# liuyang.net
KiCad netlist of a schematic drawn in Altium Designer
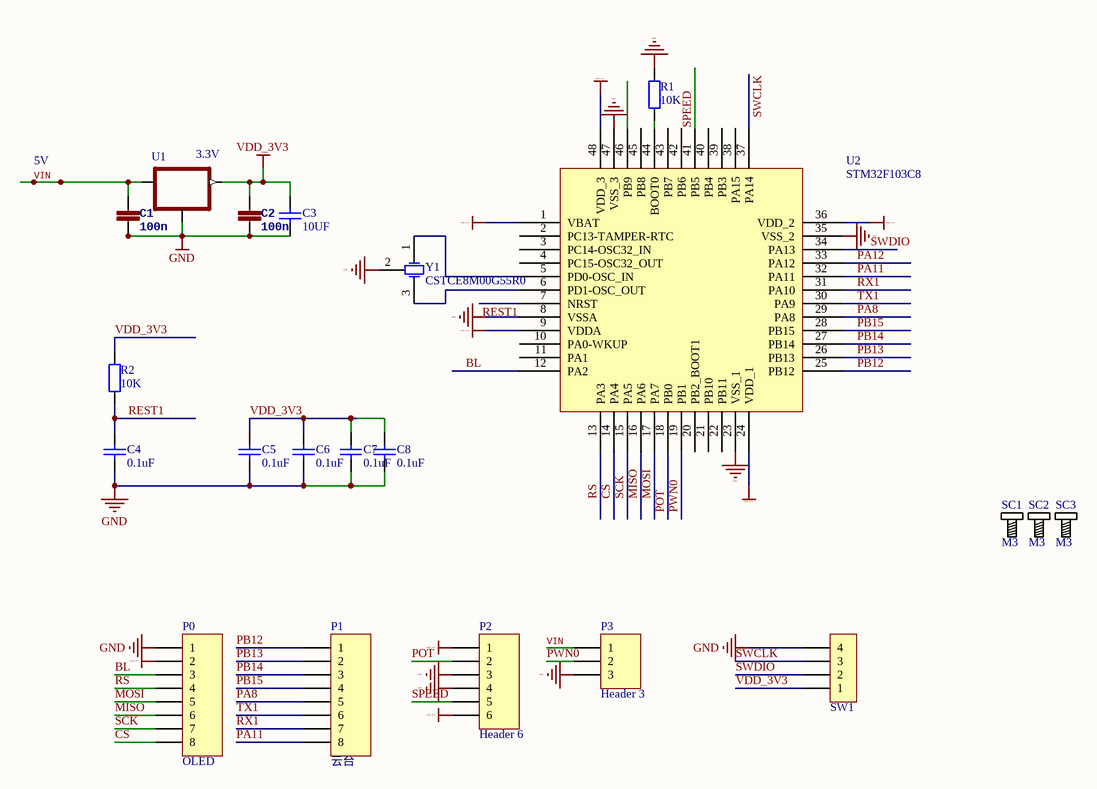
[diagram p0: liuyang.SchDoc]

(export (version "E")
  (design (tool "Eeschema 10.0.6"))
  (components
    (comp (ref "C1")
      (value "100n")
      (footprint "C0603")
      (description "CAPACITOR, European symbol")
      (libsource (lib "rcl") (part "C-EUC0603"))
    )
    (comp (ref "C2")
      (value "100n")
      (footprint "C0603")
      (description "CAPACITOR, European symbol")
      (libsource (lib "rcl") (part "C-EUC0603"))
    )
    (comp (ref "C3")
      (value "10UF")
      (footprint "C0603")
      (description "Capacitor")
      (fields (field (name "PUBLISHER") "Altium Limited"))
      (libsource (lib "Miscellaneous Devices") (part "Cap"))
    )
    (comp (ref "C4")
      (value "0.1uF")
      (footprint "C0603")
      (description "Capacitor")
      (fields (field (name "PUBLISHER") "Altium Limited"))
      (libsource (lib "Miscellaneous Devices") (part "Cap"))
    )
    (comp (ref "C5")
      (value "0.1uF")
      (footprint "C0603")
      (description "Capacitor")
      (fields (field (name "Comment") "10UF") (field (name "PUBLISHER") "Altium Limited"))
      (libsource (lib "Miscellaneous Devices") (part "Cap"))
    )
    (comp (ref "C6")
      (value "0.1uF")
      (footprint "C0603")
      (description "Capacitor")
      (fields (field (name "PUBLISHER") "Altium Limited"))
      (libsource (lib "Miscellaneous Devices") (part "Cap"))
    )
    (comp (ref "C7")
      (value "0.1uF")
      (footprint "C0603")
      (description "Capacitor")
      (fields (field (name "PUBLISHER") "Altium Limited"))
      (libsource (lib "Miscellaneous Devices") (part "Cap"))
    )
    (comp (ref "C8")
      (value "0.1uF")
      (footprint "C0603")
      (description "Capacitor")
      (fields (field (name "PUBLISHER") "Altium Limited"))
      (libsource (lib "Miscellaneous Devices") (part "Cap"))
    )
    (comp (ref "P0")
      (value "OLED")
      (footprint "DF13-1.25-8A")
      (description "Header, 8-Pin")
      (fields (field (name "PUBLISHER") "Altium Limited"))
      (libsource (lib "Miscellaneous Connectors") (part "Header 8"))
    )
    (comp (ref "P1")
      (value "云台")
      (footprint "DF13-1.25-8A")
      (description "Header, 8-Pin")
      (fields (field (name "PUBLISHER") "Altium Limited"))
      (libsource (lib "Miscellaneous Connectors") (part "Header 8"))
    )
    (comp (ref "P2")
      (value "Header 6")
      (footprint "DF13-1.25-6A")
      (description "Header, 6-Pin")
      (fields (field (name "PUBLISHER") "Altium Limited"))
      (libsource (lib "Miscellaneous Connectors") (part "Header 6"))
    )
    (comp (ref "P3")
      (value "Header 3")
      (footprint "DF13-1.25-3A")
      (description "Header, 3-Pin")
      (fields (field (name "PUBLISHER") "Altium Limited"))
      (libsource (lib "Miscellaneous Connectors") (part "Header 3"))
    )
    (comp (ref "R1")
      (value "10K")
      (footprint "R0603")
      (description "Resistor")
      (fields (field (name "PUBLISHER") "Altium Limited"))
      (libsource (lib "") (part "Res2_1"))
    )
    (comp (ref "R2")
      (value "10K")
      (footprint "R0603")
      (description "Resistor")
      (fields (field (name "PUBLISHER") "Altium Limited"))
      (libsource (lib "Miscellaneous Devices") (part "Res2"))
    )
    (comp (ref "SC1")
      (value "M3")
      (footprint "MYLIB:SCRREW_M3")
      (description "Screw")
      (libsource (lib "MY") (part "Screw_M3"))
    )
    (comp (ref "SC2")
      (value "M3")
      (footprint "SCRREW_M3")
      (description "Screw")
      (libsource (lib "MY") (part "Screw_M3"))
    )
    (comp (ref "SC3")
      (value "M3")
      (footprint "SCRREW_M3")
      (description "Screw")
      (libsource (lib "MY") (part "Screw_M3"))
    )
    (comp (ref "SW1") (value "CON4") (footprint "DF13-1.25-4A") (libsource (lib "原理图封装库") (part "CON4")))
    (comp (ref "U1") (value "3.3V") (footprint "SOT23") (libsource (lib "BGC1.0") (part "XC6206")))
    (comp (ref "U2")
      (value "STM32F103C8")
      (footprint "ST_LQFP48")
      (libsource (lib "airtops-L") (part "STM32F103C8"))
    )
    (comp (ref "Y1")
      (value "CSTCE8M00G55R0")
      (footprint "CRYSMD3.2X1.3")
      (libsource (lib "airtops-L") (part "XTAL-3"))
    )
  )
  (nets
    (net (code "1") (name "/BL") (class "Default")
      (node (ref "P0") (pin "3") (pinfunction "3_3") (pintype "passive"))
      (node (ref "U2") (pin "12") (pinfunction "PA2_12") (pintype "passive"))
    )
    (net (code "2") (name "/CS") (class "Default")
      (node (ref "P0") (pin "8") (pinfunction "8_8") (pintype "passive"))
      (node (ref "U2") (pin "14") (pinfunction "PA4_14") (pintype "passive"))
    )
    (net (code "3") (name "/MISO") (class "Default")
      (node (ref "P0") (pin "6") (pinfunction "6_6") (pintype "passive"))
      (node (ref "U2") (pin "16") (pinfunction "PA6_16") (pintype "passive"))
    )
    (net (code "4") (name "/MOSI") (class "Default")
      (node (ref "P0") (pin "5") (pinfunction "5_5") (pintype "passive"))
      (node (ref "U2") (pin "17") (pinfunction "PA7_17") (pintype "passive"))
    )
    (net (code "5") (name "/PA8") (class "Default")
      (node (ref "P1") (pin "5") (pinfunction "5_5") (pintype "passive"))
      (node (ref "U2") (pin "29") (pinfunction "PA8_29") (pintype "passive"))
    )
    (net (code "6") (name "/PA11") (class "Default")
      (node (ref "P1") (pin "8") (pinfunction "8_8") (pintype "passive"))
      (node (ref "U2") (pin "32") (pinfunction "PA11_32") (pintype "passive"))
    )
    (net (code "7") (name "/PA12") (class "Default")
      (node (ref "U2") (pin "33") (pinfunction "PA12_33") (pintype "passive"))
    )
    (net (code "8") (name "/PB12") (class "Default")
      (node (ref "P1") (pin "1") (pinfunction "1_1") (pintype "passive"))
      (node (ref "U2") (pin "25") (pinfunction "PB12_25") (pintype "passive"))
    )
    (net (code "9") (name "/PB13") (class "Default")
      (node (ref "P1") (pin "2") (pinfunction "2_2") (pintype "passive"))
      (node (ref "U2") (pin "26") (pinfunction "PB13_26") (pintype "passive"))
    )
    (net (code "10") (name "/PB14") (class "Default")
      (node (ref "P1") (pin "3") (pinfunction "3_3") (pintype "passive"))
      (node (ref "U2") (pin "27") (pinfunction "PB14_27") (pintype "passive"))
    )
    (net (code "11") (name "/PB15") (class "Default")
      (node (ref "P1") (pin "4") (pinfunction "4_4") (pintype "passive"))
      (node (ref "U2") (pin "28") (pinfunction "PB15_28") (pintype "passive"))
    )
    (net (code "12") (name "/POT") (class "Default")
      (node (ref "P2") (pin "2") (pinfunction "2_2") (pintype "passive"))
      (node (ref "U2") (pin "18") (pinfunction "PB0_18") (pintype "passive"))
    )
    (net (code "13") (name "/PWN0") (class "Default")
      (node (ref "P3") (pin "2") (pinfunction "2_2") (pintype "passive"))
      (node (ref "U2") (pin "19") (pinfunction "PB1_19") (pintype "passive"))
    )
    (net (code "14") (name "/REST1") (class "Default")
      (node (ref "C4") (pin "2") (pinfunction "2_2") (pintype "passive"))
      (node (ref "R2") (pin "1") (pinfunction "1_1") (pintype "passive"))
      (node (ref "U2") (pin "7") (pinfunction "NRST_7") (pintype "passive"))
    )
    (net (code "15") (name "/RS") (class "Default")
      (node (ref "P0") (pin "4") (pinfunction "4_4") (pintype "passive"))
      (node (ref "U2") (pin "13") (pinfunction "PA3_13") (pintype "passive"))
    )
    (net (code "16") (name "/RX1") (class "Default")
      (node (ref "P1") (pin "7") (pinfunction "7_7") (pintype "passive"))
      (node (ref "U2") (pin "31") (pinfunction "PA10_31") (pintype "passive"))
    )
    (net (code "17") (name "/SCK") (class "Default")
      (node (ref "P0") (pin "7") (pinfunction "7_7") (pintype "passive"))
      (node (ref "U2") (pin "15") (pinfunction "PA5_15") (pintype "passive"))
    )
    (net (code "18") (name "/SPEED") (class "Default")
      (node (ref "P2") (pin "5") (pinfunction "5_5") (pintype "passive"))
      (node (ref "U2") (pin "41") (pinfunction "PB5_41") (pintype "passive"))
    )
    (net (code "19") (name "/SWCLK") (class "Default")
      (node (ref "SW1") (pin "3") (pinfunction "3_3") (pintype "passive"))
      (node (ref "U2") (pin "37") (pinfunction "PA14_37") (pintype "passive"))
    )
    (net (code "20") (name "/SWDIO") (class "Default")
      (node (ref "SW1") (pin "2") (pinfunction "2_2") (pintype "passive"))
      (node (ref "U2") (pin "34") (pinfunction "PA13_34") (pintype "passive"))
    )
    (net (code "21") (name "/TX1") (class "Default")
      (node (ref "P1") (pin "6") (pinfunction "6_6") (pintype "passive"))
      (node (ref "U2") (pin "30") (pinfunction "PA9_30") (pintype "passive"))
    )
    (net (code "22") (name "/VIN") (class "Default")
      (node (ref "C1") (pin "1") (pinfunction "1_1") (pintype "passive"))
      (node (ref "P3") (pin "1") (pinfunction "1_1") (pintype "passive"))
      (node (ref "U1") (pin "3") (pinfunction "IN_3") (pintype "passive"))
    )
    (net (code "23") (name "GND") (class "Default")
      (node (ref "C1") (pin "2") (pinfunction "2_2") (pintype "passive"))
      (node (ref "C2") (pin "2") (pinfunction "2_2") (pintype "passive"))
      (node (ref "C3") (pin "1") (pinfunction "1_1") (pintype "passive"))
      (node (ref "C4") (pin "1") (pinfunction "1_1") (pintype "passive"))
      (node (ref "C5") (pin "1") (pinfunction "1_1") (pintype "passive"))
      (node (ref "C6") (pin "1") (pinfunction "1_1") (pintype "passive"))
      (node (ref "C7") (pin "1") (pinfunction "1_1") (pintype "passive"))
      (node (ref "C8") (pin "1") (pinfunction "1_1") (pintype "passive"))
      (node (ref "P0") (pin "1") (pinfunction "1_1") (pintype "passive"))
      (node (ref "P2") (pin "3") (pinfunction "3_3") (pintype "passive"))
      (node (ref "P2") (pin "4") (pinfunction "4_4") (pintype "passive"))
      (node (ref "P3") (pin "3") (pinfunction "3_3") (pintype "passive"))
      (node (ref "R1") (pin "1") (pinfunction "1_1") (pintype "passive"))
      (node (ref "SW1") (pin "4") (pinfunction "4_4") (pintype "passive"))
      (node (ref "U1") (pin "1") (pinfunction "GND_1") (pintype "passive"))
      (node (ref "U2") (pin "23") (pinfunction "VSS_1_23") (pintype "passive"))
      (node (ref "U2") (pin "35") (pinfunction "VSS_2_35") (pintype "passive"))
      (node (ref "U2") (pin "47") (pinfunction "VSS_3_47") (pintype "passive"))
      (node (ref "U2") (pin "8") (pinfunction "VSSA_8") (pintype "passive"))
      (node (ref "Y1") (pin "2") (pinfunction "GND_2") (pintype "passive"))
    )
    (net (code "24") (name "Net-(U2-BOOT0)") (class "Default")
      (node (ref "R1") (pin "2") (pinfunction "2_2") (pintype "passive"))
      (node (ref "U2") (pin "44") (pinfunction "BOOT0_44") (pintype "passive"))
    )
    (net (code "25") (name "Net-(U2-PD0-OSC_IN)") (class "Default")
      (node (ref "U2") (pin "5") (pinfunction "PD0-OSC_IN_5") (pintype "passive"))
      (node (ref "Y1") (pin "1") (pinfunction "OSC1_1") (pintype "passive"))
    )
    (net (code "26") (name "Net-(U2-PD1-OSC_OUT)") (class "Default")
      (node (ref "U2") (pin "6") (pinfunction "PD1-OSC_OUT_6") (pintype "passive"))
      (node (ref "Y1") (pin "3") (pinfunction "OSC2_3") (pintype "passive"))
    )
    (net (code "27") (name "VDD_3V3") (class "Default")
      (node (ref "C2") (pin "1") (pinfunction "1_1") (pintype "passive"))
      (node (ref "C3") (pin "2") (pinfunction "2_2") (pintype "passive"))
      (node (ref "C5") (pin "2") (pinfunction "2_2") (pintype "passive"))
      (node (ref "C6") (pin "2") (pinfunction "2_2") (pintype "passive"))
      (node (ref "C7") (pin "2") (pinfunction "2_2") (pintype "passive"))
      (node (ref "C8") (pin "2") (pinfunction "2_2") (pintype "passive"))
      (node (ref "P0") (pin "2") (pinfunction "2_2") (pintype "passive"))
      (node (ref "P2") (pin "1") (pinfunction "1_1") (pintype "passive"))
      (node (ref "P2") (pin "6") (pinfunction "6_6") (pintype "passive"))
      (node (ref "R2") (pin "2") (pinfunction "2_2") (pintype "passive"))
      (node (ref "SW1") (pin "1") (pinfunction "1_1") (pintype "passive"))
      (node (ref "U1") (pin "2") (pinfunction "OUT_2") (pintype "output"))
      (node (ref "U2") (pin "1") (pinfunction "VBAT_1") (pintype "passive"))
      (node (ref "U2") (pin "24") (pinfunction "VDD_1_24") (pintype "passive"))
      (node (ref "U2") (pin "36") (pinfunction "VDD_2_36") (pintype "passive"))
      (node (ref "U2") (pin "48") (pinfunction "VDD_3_48") (pintype "passive"))
      (node (ref "U2") (pin "9") (pinfunction "VDDA_9") (pintype "passive"))
    )
    (net (code "28") (name "unconnected-(U2-PA0-WKUP-Pad10)") (class "Default")
      (node (ref "U2") (pin "10") (pinfunction "PA0-WKUP_10") (pintype "passive"))
    )
    (net (code "29") (name "unconnected-(U2-PA1-Pad11)") (class "Default")
      (node (ref "U2") (pin "11") (pinfunction "PA1_11") (pintype "passive"))
    )
    (net (code "30") (name "unconnected-(U2-PA15-Pad38)") (class "Default")
      (node (ref "U2") (pin "38") (pinfunction "PA15_38") (pintype "passive"))
    )
    (net (code "31") (name "unconnected-(U2-PB2_BOOT1-Pad20)") (class "Default")
      (node (ref "U2") (pin "20") (pinfunction "PB2_BOOT1_20") (pintype "passive"))
    )
    (net (code "32") (name "unconnected-(U2-PB3-Pad39)") (class "Default")
      (node (ref "U2") (pin "39") (pinfunction "PB3_39") (pintype "passive"))
    )
    (net (code "33") (name "unconnected-(U2-PB4-Pad40)") (class "Default")
      (node (ref "U2") (pin "40") (pinfunction "PB4_40") (pintype "passive"))
    )
    (net (code "34") (name "unconnected-(U2-PB6-Pad42)") (class "Default")
      (node (ref "U2") (pin "42") (pinfunction "PB6_42") (pintype "passive"))
    )
    (net (code "35") (name "unconnected-(U2-PB7-Pad43)") (class "Default")
      (node (ref "U2") (pin "43") (pinfunction "PB7_43") (pintype "passive"))
    )
    (net (code "36") (name "unconnected-(U2-PB8-Pad45)") (class "Default")
      (node (ref "U2") (pin "45") (pinfunction "PB8_45") (pintype "passive"))
    )
    (net (code "37") (name "unconnected-(U2-PB9-Pad46)") (class "Default")
      (node (ref "U2") (pin "46") (pinfunction "PB9_46") (pintype "passive"))
    )
    (net (code "38") (name "unconnected-(U2-PB10-Pad21)") (class "Default")
      (node (ref "U2") (pin "21") (pinfunction "PB10_21") (pintype "passive"))
    )
    (net (code "39") (name "unconnected-(U2-PB11-Pad22)") (class "Default")
      (node (ref "U2") (pin "22") (pinfunction "PB11_22") (pintype "passive"))
    )
    (net (code "40") (name "unconnected-(U2-PC13-TAMPER-RTC-Pad2)") (class "Default")
      (node (ref "U2") (pin "2") (pinfunction "PC13-TAMPER-RTC_2") (pintype "passive"))
    )
    (net (code "41") (name "unconnected-(U2-PC14-OSC32_IN-Pad3)") (class "Default")
      (node (ref "U2") (pin "3") (pinfunction "PC14-OSC32_IN_3") (pintype "passive"))
    )
    (net (code "42") (name "unconnected-(U2-PC15-OSC32_OUT-Pad4)") (class "Default")
      (node (ref "U2") (pin "4") (pinfunction "PC15-OSC32_OUT_4") (pintype "passive"))
    )
  )
)
